# ButtonsMiniBoard.net
KiCad netlist of a schematic drawn in EAGLE
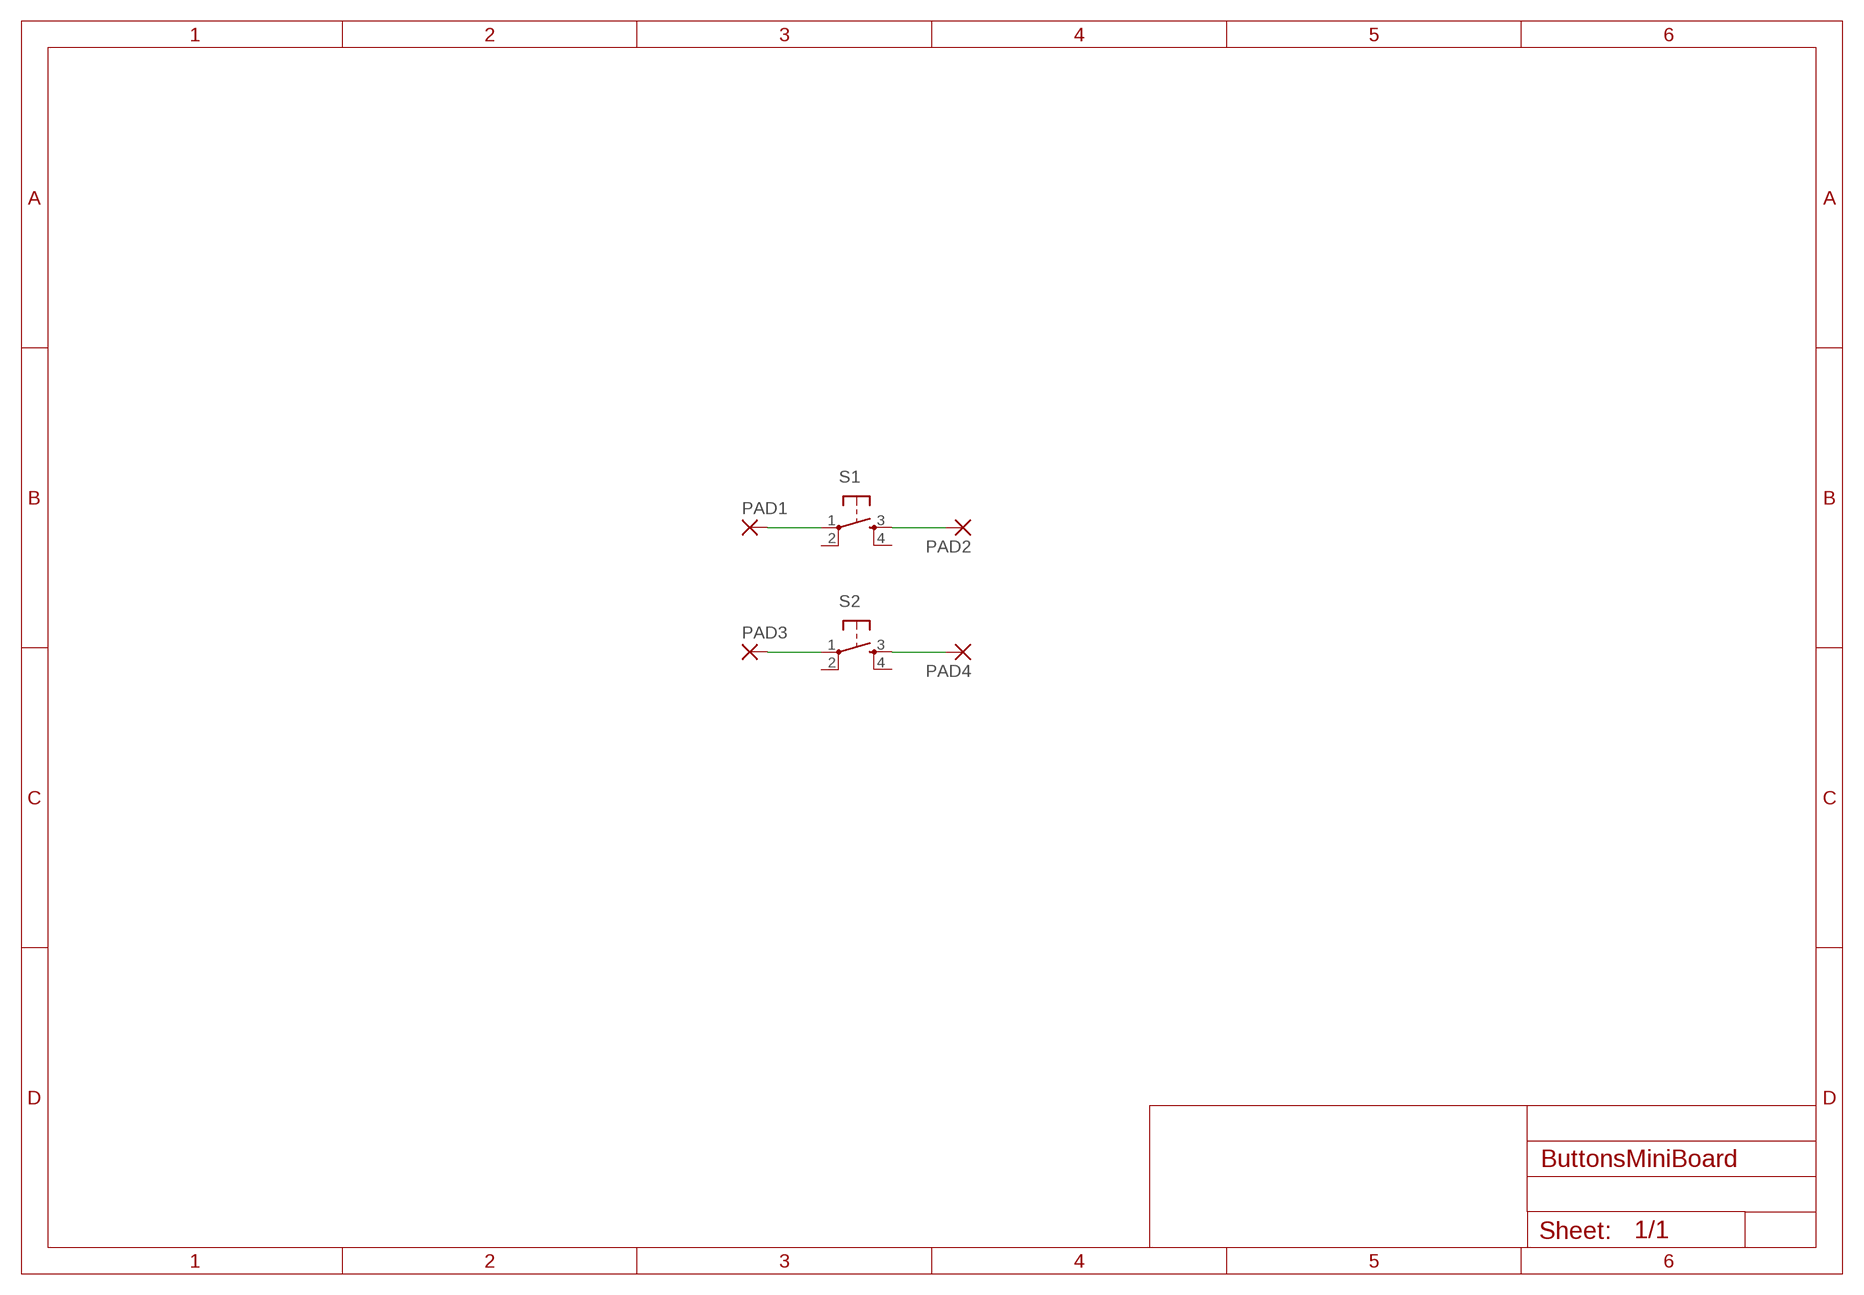
[diagram p0: schematic, sheet 1]

(export (version "E")
  (design (tool "Eeschema 10.0.6"))
  (components
    (comp (ref "PAD1")
      (value "2,15/1,0")
      (footprint "eagle-import:2,15_1,0")
      (libsource (lib "eagle-import") (part "2,15/1,0"))
    )
    (comp (ref "PAD2")
      (value "2,15/1,0")
      (footprint "eagle-import:2,15_1,0")
      (libsource (lib "eagle-import") (part "2,15/1,0"))
    )
    (comp (ref "PAD3")
      (value "2,15/1,0")
      (footprint "eagle-import:2,15_1,0")
      (libsource (lib "eagle-import") (part "2,15/1,0"))
    )
    (comp (ref "PAD4")
      (value "2,15/1,0")
      (footprint "eagle-import:2,15_1,0")
      (libsource (lib "eagle-import") (part "2,15/1,0"))
    )
    (comp (ref "S1")
      (value "TAC_SWITCHPTH")
      (footprint "eagle-import:TACTILE-PTH")
      (libsource (lib "eagle-import") (part "TAC_SWITCHPTH"))
    )
    (comp (ref "S2")
      (value "TAC_SWITCHPTH")
      (footprint "eagle-import:TACTILE-PTH")
      (libsource (lib "eagle-import") (part "TAC_SWITCHPTH"))
    )
  )
  (nets
    (net (code "1") (name "Net-(PAD1-P)") (class "Default")
      (node (ref "PAD1") (pin "1") (pinfunction "P_1") (pintype "passive"))
      (node (ref "S1") (pin "1") (pinfunction "1_1") (pintype "passive"))
    )
    (net (code "2") (name "Net-(PAD2-P)") (class "Default")
      (node (ref "PAD2") (pin "1") (pinfunction "P_1") (pintype "passive"))
      (node (ref "S1") (pin "3") (pinfunction "3_3") (pintype "passive"))
    )
    (net (code "3") (name "Net-(PAD3-P)") (class "Default")
      (node (ref "PAD3") (pin "1") (pinfunction "P_1") (pintype "passive"))
      (node (ref "S2") (pin "1") (pinfunction "1_1") (pintype "passive"))
    )
    (net (code "4") (name "Net-(PAD4-P)") (class "Default")
      (node (ref "PAD4") (pin "1") (pinfunction "P_1") (pintype "passive"))
      (node (ref "S2") (pin "3") (pinfunction "3_3") (pintype "passive"))
    )
    (net (code "5") (name "unconnected-(S1-Pad2)") (class "Default")
      (node (ref "S1") (pin "2") (pinfunction "2_2") (pintype "passive"))
    )
    (net (code "6") (name "unconnected-(S1-Pad4)") (class "Default")
      (node (ref "S1") (pin "4") (pinfunction "4_4") (pintype "passive"))
    )
    (net (code "7") (name "unconnected-(S2-Pad2)") (class "Default")
      (node (ref "S2") (pin "2") (pinfunction "2_2") (pintype "passive"))
    )
    (net (code "8") (name "unconnected-(S2-Pad4)") (class "Default")
      (node (ref "S2") (pin "4") (pinfunction "4_4") (pintype "passive"))
    )
  )
)
